# SC_ControlV2_0.net
KiCad netlist of a schematic drawn in Altium Designer
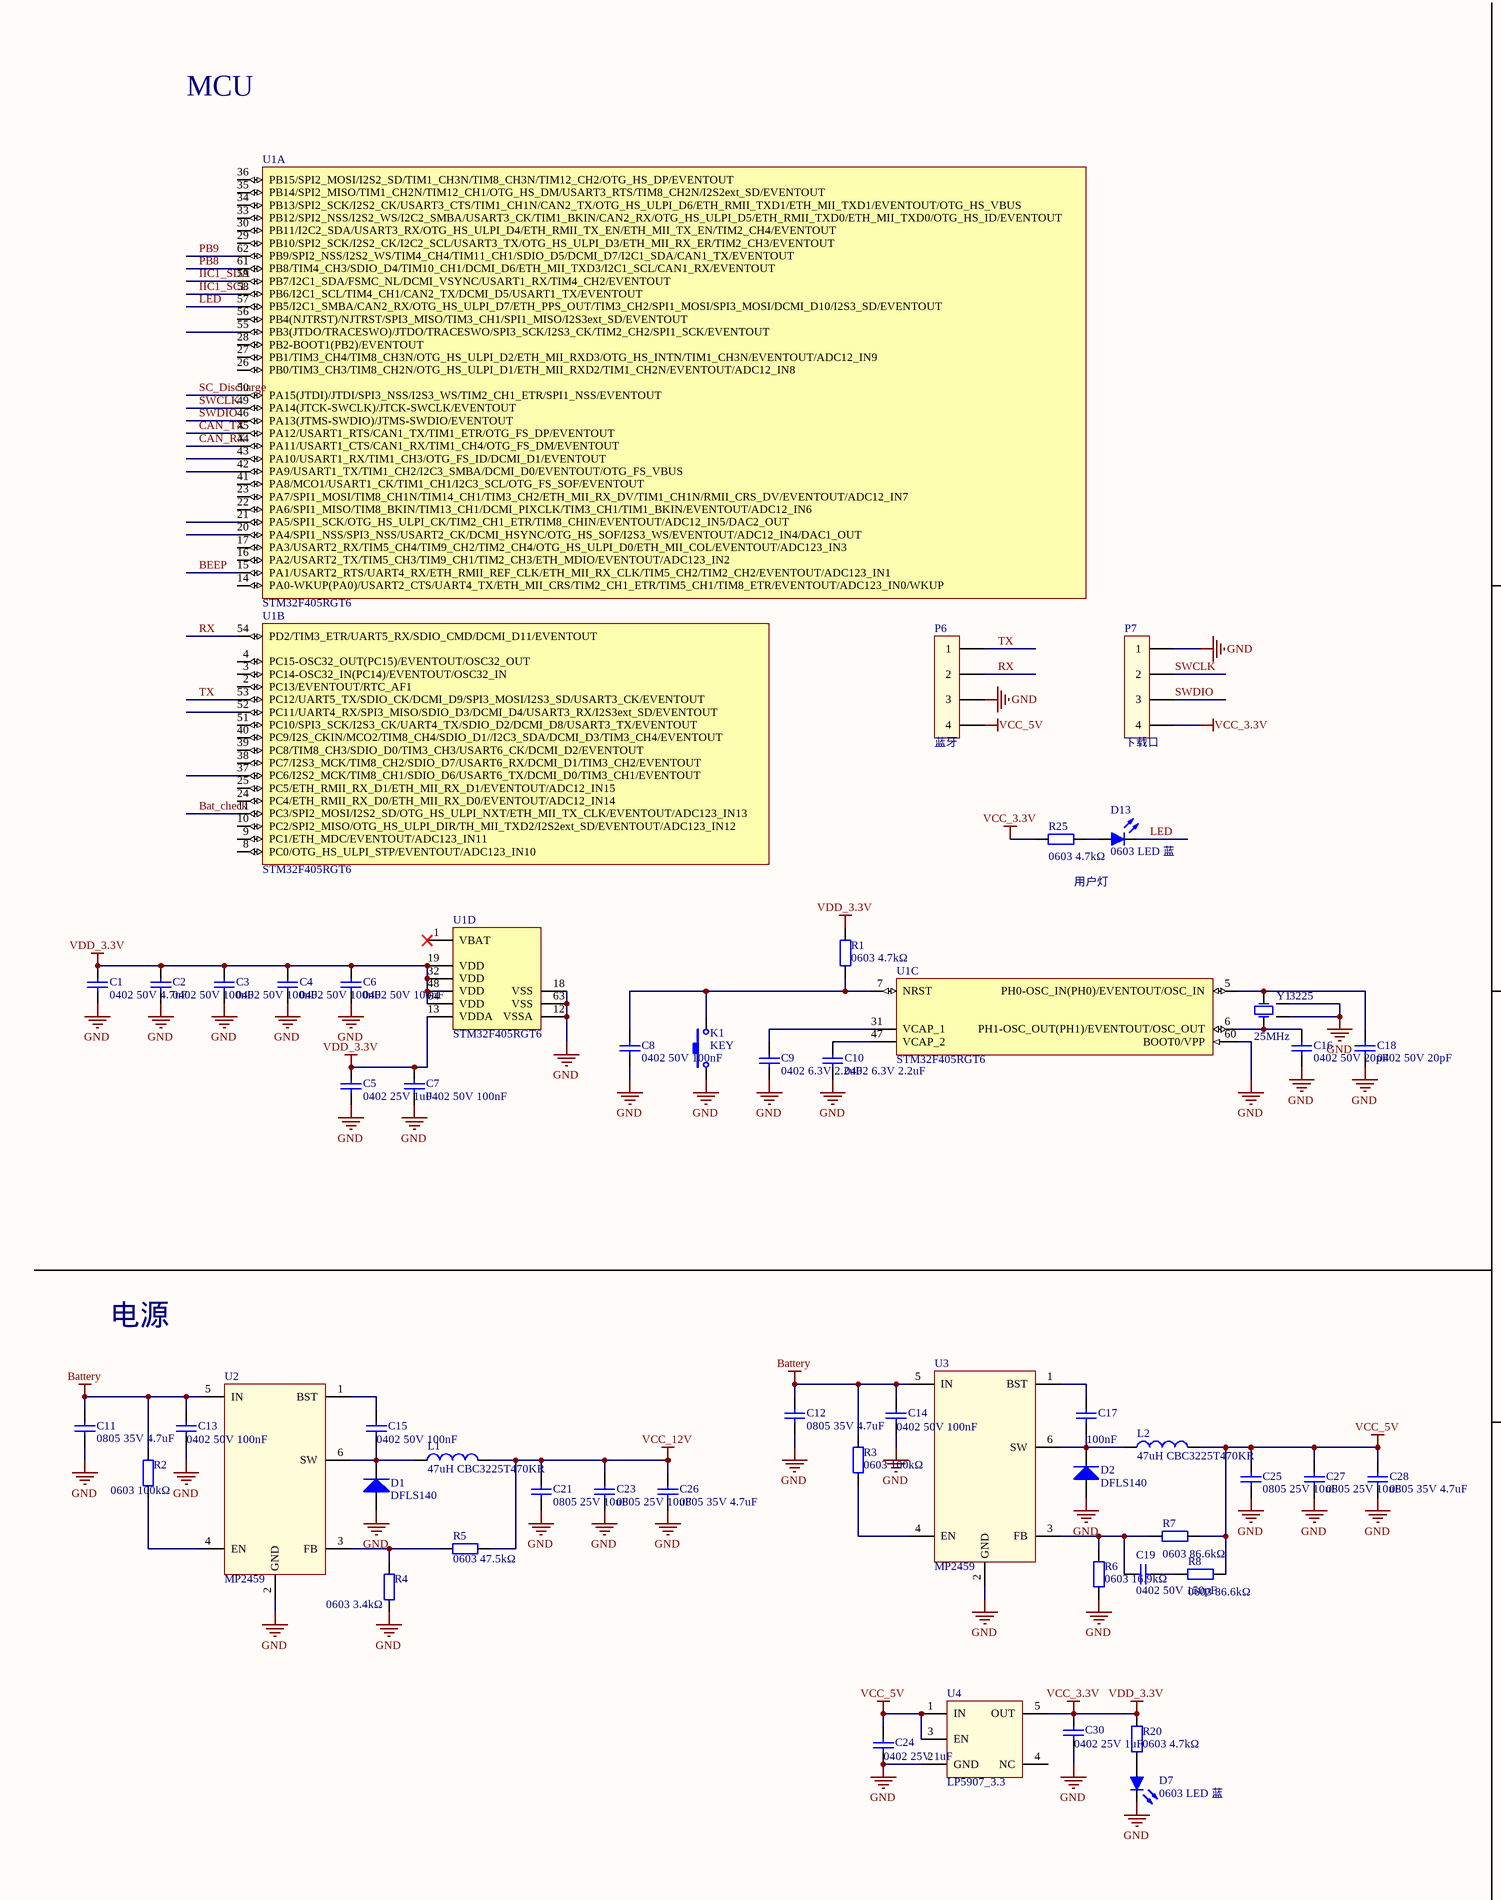
[diagram p0: SC_ControlV2.0.SchDoc, left]
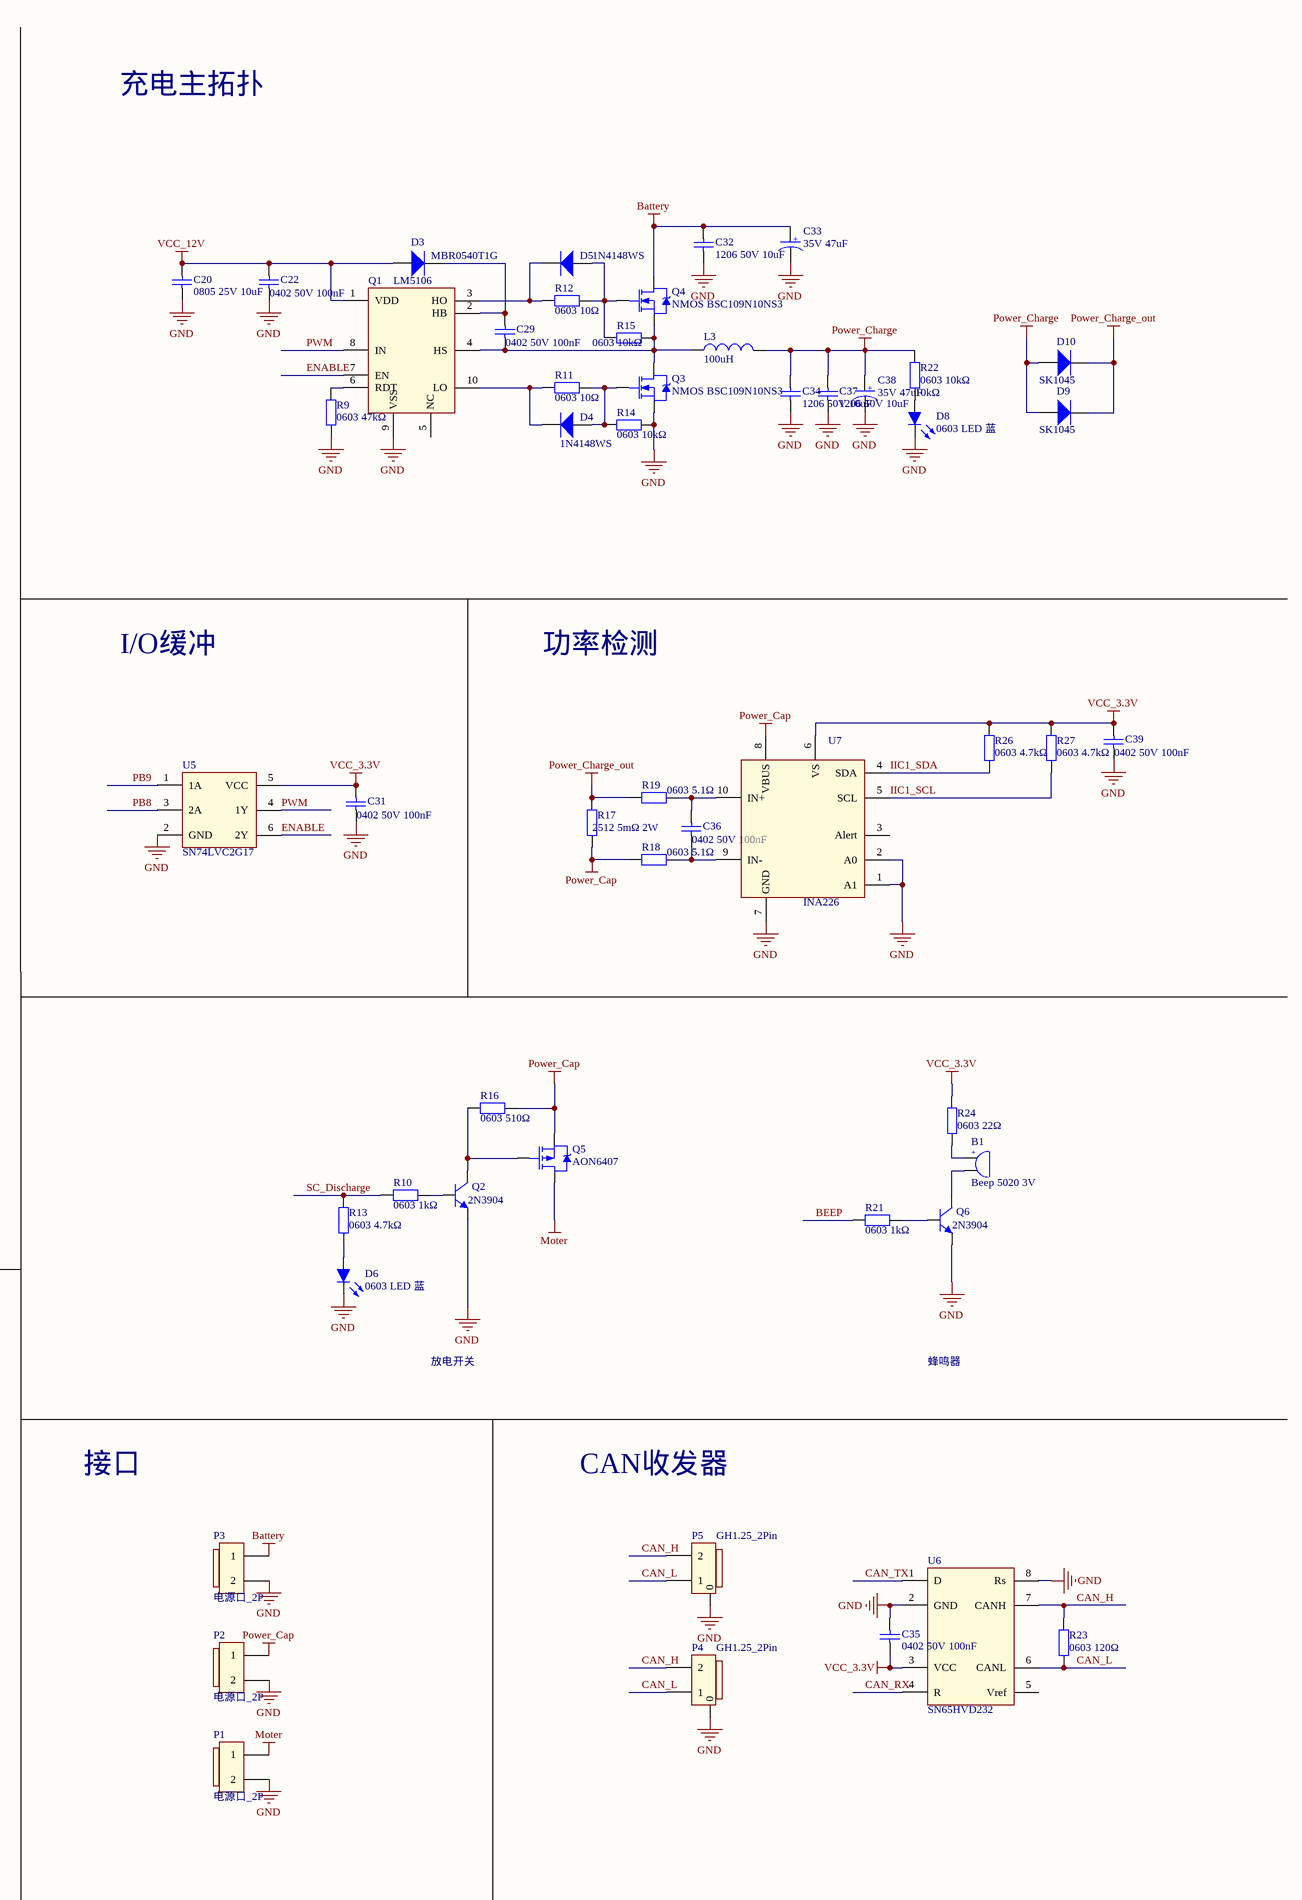
[diagram p1: SC_ControlV2.0.SchDoc, right]

(export (version "E")
  (design (tool "Eeschema 10.0.6"))
  (components
    (comp (ref "B1")
      (value "Beep 5020 3V")
      (footprint "Beep 5020")
      (libsource (lib "MyLib_zzy") (part "Beep"))
    )
    (comp (ref "C1") (value "0402 50V 4.7uF") (footprint "0402_C") (libsource (lib "MyLib_zzy") (part "Cap")))
    (comp (ref "C2") (value "0402 50V 100nF") (footprint "0402_C") (libsource (lib "MyLib_zzy") (part "Cap")))
    (comp (ref "C3") (value "0402 50V 100nF") (footprint "0402_C") (libsource (lib "MyLib_zzy") (part "Cap")))
    (comp (ref "C4") (value "0402 50V 100nF") (footprint "0402_C") (libsource (lib "MyLib_zzy") (part "Cap")))
    (comp (ref "C5") (value "0402 25V 1uF") (footprint "0402_C") (libsource (lib "MyLib_zzy") (part "Cap")))
    (comp (ref "C6") (value "0402 50V 100nF") (footprint "0402_C") (libsource (lib "MyLib_zzy") (part "Cap")))
    (comp (ref "C7") (value "0402 50V 100nF") (footprint "0402_C") (libsource (lib "MyLib_zzy") (part "Cap")))
    (comp (ref "C8") (value "0402 50V 100nF") (footprint "0402_C") (libsource (lib "MyLib_zzy") (part "Cap")))
    (comp (ref "C9")
      (value "0402 6.3V 2.2uF")
      (footprint "0402_C")
      (libsource (lib "MyLib_zzy") (part "Cap"))
    )
    (comp (ref "C10")
      (value "0402 6.3V 2.2uF")
      (footprint "0402_C")
      (libsource (lib "MyLib_zzy") (part "Cap"))
    )
    (comp (ref "C11")
      (value "0805 35V 4.7uF")
      (footprint "0805_C")
      (libsource (lib "MyLib_zzy") (part "Cap"))
    )
    (comp (ref "C12")
      (value "0805 35V 4.7uF")
      (footprint "0805_C")
      (libsource (lib "MyLib_zzy") (part "Cap"))
    )
    (comp (ref "C13")
      (value "0402 50V 100nF")
      (footprint "0402_C")
      (libsource (lib "MyLib_zzy") (part "Cap"))
    )
    (comp (ref "C14")
      (value "0402 50V 100nF")
      (footprint "0402_C")
      (libsource (lib "MyLib_zzy") (part "Cap"))
    )
    (comp (ref "C15")
      (value "0402 50V 100nF")
      (footprint "0402_C")
      (libsource (lib "MyLib_zzy") (part "Cap"))
    )
    (comp (ref "C16") (value "0402 50V 20pF") (footprint "0402_C") (libsource (lib "MyLib_zzy") (part "Cap")))
    (comp (ref "C17")
      (value "0402 50V 100nF")
      (footprint "0402_C")
      (fields (field (name "CAP") "100nF"))
      (libsource (lib "MyLib_zzy") (part "Cap"))
    )
    (comp (ref "C18") (value "0402 50V 20pF") (footprint "0402_C") (libsource (lib "MyLib_zzy") (part "Cap")))
    (comp (ref "C19")
      (value "0402 50V 150pF")
      (footprint "0603_C")
      (libsource (lib "MyLib_zzy") (part "Cap"))
    )
    (comp (ref "C20") (value "0805 25V 10uF") (footprint "0805_C") (libsource (lib "MyLib_zzy") (part "Cap")))
    (comp (ref "C21") (value "0805 25V 10uF") (footprint "0805_C") (libsource (lib "MyLib_zzy") (part "Cap")))
    (comp (ref "C22") (value "0402 50V 100nF") (footprint "0402_C") (libsource (lib "") (part "Cap_1")))
    (comp (ref "C23") (value "0805 25V 10uF") (footprint "0805_C") (libsource (lib "MyLib_zzy") (part "Cap")))
    (comp (ref "C24") (value "0402 25V 1uF") (footprint "0402_C") (libsource (lib "MyLib_zzy") (part "Cap")))
    (comp (ref "C25") (value "0805 25V 10uF") (footprint "0805_C") (libsource (lib "MyLib_zzy") (part "Cap")))
    (comp (ref "C26")
      (value "0805 35V 4.7uF")
      (footprint "0805_C")
      (libsource (lib "MyLib_zzy") (part "Cap"))
    )
    (comp (ref "C27") (value "0805 25V 10uF") (footprint "0805_C") (libsource (lib "MyLib_zzy") (part "Cap")))
    (comp (ref "C28")
      (value "0805 35V 4.7uF")
      (footprint "0805_C")
      (libsource (lib "MyLib_zzy") (part "Cap"))
    )
    (comp (ref "C29") (value "0402 50V 100nF") (footprint "0402_C") (libsource (lib "") (part "Cap_1")))
    (comp (ref "C30") (value "0402 25V 1uF") (footprint "0402_C") (libsource (lib "MyLib_zzy") (part "Cap")))
    (comp (ref "C31") (value "0402 50V 100nF") (footprint "0402_C") (libsource (lib "") (part "Cap_1")))
    (comp (ref "C32") (value "1206 50V 10uF") (footprint "1206_C") (libsource (lib "MyLib_zzy") (part "Cap")))
    (comp (ref "C33") (value "35V 47uF") (footprint "贴片铝电解_8") (libsource (lib "MyLib_zzy") (part "铝电解")))
    (comp (ref "C34") (value "1206 50V 10uF") (footprint "1206_C") (libsource (lib "MyLib_zzy") (part "Cap")))
    (comp (ref "C35")
      (value "0402 50V 100nF")
      (footprint "0402_C")
      (libsource (lib "MyLib_zzy") (part "Cap"))
    )
    (comp (ref "C36") (value "0402 50V 100nF") (footprint "0402_C") (libsource (lib "") (part "Cap_1")))
    (comp (ref "C37") (value "1206 50V 10uF") (footprint "1206_C") (libsource (lib "MyLib_zzy") (part "Cap")))
    (comp (ref "C38") (value "35V 47uF") (footprint "贴片铝电解_8") (libsource (lib "MyLib_zzy") (part "铝电解")))
    (comp (ref "C39") (value "0402 50V 100nF") (footprint "0402_C") (libsource (lib "") (part "Cap_1")))
    (comp (ref "D1")
      (value "DFLS140")
      (footprint "POWERDI_123")
      (libsource (lib "MyLib_zzy") (part "肖特基二极管"))
    )
    (comp (ref "D2")
      (value "DFLS140")
      (footprint "POWERDI_123")
      (libsource (lib "MyLib_zzy") (part "肖特基二极管"))
    )
    (comp (ref "D3")
      (value "MBR0540T1G")
      (footprint "SOD_123F")
      (libsource (lib "MyLib_zzy") (part "肖特基二极管"))
    )
    (comp (ref "D4") (value "1N4148WS") (footprint "SOD_323F") (libsource (lib "MyLib_zzy") (part "开关二极管")))
    (comp (ref "D5") (value "1N4148WS") (footprint "SOD_323F") (libsource (lib "MyLib_zzy") (part "开关二极管")))
    (comp (ref "D6") (value "0603 LED 蓝") (footprint "0603_LED") (libsource (lib "MyLib_zzy") (part "LED")))
    (comp (ref "D7") (value "0603 LED 蓝") (footprint "0603_LED") (libsource (lib "MyLib_zzy") (part "LED")))
    (comp (ref "D8") (value "0603 LED 蓝") (footprint "0603_LED") (libsource (lib "MyLib_zzy") (part "LED")))
    (comp (ref "D9")
      (value "SK1045")
      (footprint "MyLib_zzy:SMC")
      (libsource (lib "MyLib_zzy") (part "肖特基二极管"))
    )
    (comp (ref "D10")
      (value "SK1045")
      (footprint "MyLib_zzy:SMC")
      (libsource (lib "MyLib_zzy") (part "肖特基二极管"))
    )
    (comp (ref "D13") (value "0603 LED 蓝") (footprint "0603_LED") (libsource (lib "MyLib_zzy") (part "LED")))
    (comp (ref "K1") (value "KEY") (footprint "按键_3*4") (libsource (lib "MyLib_zzy") (part "按键_小")))
    (comp (ref "L1")
      (value "47uH CBC3225T470KR")
      (footprint "1210_L")
      (libsource (lib "MyLib_zzy") (part "电感"))
    )
    (comp (ref "L2")
      (value "47uH CBC3225T470KR")
      (footprint "1210_L")
      (libsource (lib "MyLib_zzy") (part "电感"))
    )
    (comp (ref "L3") (value "100uH") (footprint "绕线电感_14mm") (libsource (lib "MyLib_zzy") (part "电感")))
    (comp (ref "P1") (value "电源口_2P") (footprint "电源口_2P") (libsource (lib "MyLib_zzy") (part "电源口_2P")))
    (comp (ref "P2") (value "电源口_2P") (footprint "电源口_2P") (libsource (lib "MyLib_zzy") (part "电源口_2P")))
    (comp (ref "P3") (value "电源口_2P") (footprint "电源口_2P") (libsource (lib "MyLib_zzy") (part "电源口_2P")))
    (comp (ref "P4")
      (value "GH1.25_2Pin")
      (footprint "GH1.25_2Pin")
      (libsource (lib "MyLib_zzy") (part "GH1.25_2Pin"))
    )
    (comp (ref "P5")
      (value "GH1.25_2Pin")
      (footprint "GH1.25_2Pin")
      (libsource (lib "MyLib_zzy") (part "GH1.25_2Pin"))
    )
    (comp (ref "P6") (value "蓝牙") (footprint "HDR_4Pin") (libsource (lib "MyLib_zzy") (part "HDR_4Pin")))
    (comp (ref "P7") (value "下载口") (footprint "HDR_4Pin") (libsource (lib "MyLib_zzy") (part "HDR_4Pin")))
    (comp (ref "Q1") (value "LM5106") (footprint "VSSOP10") (libsource (lib "MyLib_zzy") (part "LM5106")))
    (comp (ref "Q2") (value "2N3904") (footprint "SOT23_3") (libsource (lib "MyLib_zzy") (part "NPN")))
    (comp (ref "Q3")
      (value "NMOS BSC109N10NS3")
      (footprint "PG_TDSON_8")
      (libsource (lib "MyLib_zzy") (part "NMOS"))
    )
    (comp (ref "Q4")
      (value "NMOS BSC109N10NS3")
      (footprint "PG_TDSON_8")
      (libsource (lib "MyLib_zzy") (part "NMOS"))
    )
    (comp (ref "Q5") (value "AON6407") (footprint "DFN_5x6") (libsource (lib "MyLib_zzy") (part "PMOS")))
    (comp (ref "Q6") (value "2N3904") (footprint "SOT23_3") (libsource (lib "MyLib_zzy") (part "NPN")))
    (comp (ref "R1") (value "0603 4.7kΩ") (footprint "0603 _R") (libsource (lib "") (part "Res_1")))
    (comp (ref "R2") (value "0603 100kΩ") (footprint "0603 _R") (libsource (lib "") (part "Res_1")))
    (comp (ref "R3") (value "0603 100kΩ") (footprint "0603 _R") (libsource (lib "") (part "Res_2")))
    (comp (ref "R4") (value "0603 3.4kΩ") (footprint "0603 _R") (libsource (lib "") (part "Res_1")))
    (comp (ref "R5") (value "0603 47.5kΩ") (footprint "0603 _R") (libsource (lib "MyLib_zzy") (part "Res")))
    (comp (ref "R6") (value "0603 16.9kΩ") (footprint "0603 _R") (libsource (lib "") (part "Res_2")))
    (comp (ref "R7") (value "0603 86.6kΩ") (footprint "0603 _R") (libsource (lib "MyLib_zzy") (part "Res")))
    (comp (ref "R8") (value "0603 86.6kΩ") (footprint "0603 _R") (libsource (lib "MyLib_zzy") (part "Res")))
    (comp (ref "R9") (value "0603 47kΩ") (footprint "0603 _R") (libsource (lib "") (part "Res_2")))
    (comp (ref "R10") (value "0603 1kΩ") (footprint "0603 _R") (libsource (lib "MyLib_zzy") (part "Res")))
    (comp (ref "R11") (value "0603 10Ω") (footprint "0603 _R") (libsource (lib "MyLib_zzy") (part "Res")))
    (comp (ref "R12") (value "0603 10Ω") (footprint "0603 _R") (libsource (lib "MyLib_zzy") (part "Res")))
    (comp (ref "R13") (value "0603 4.7kΩ") (footprint "0603 _R") (libsource (lib "") (part "Res_1")))
    (comp (ref "R14") (value "0603 10kΩ") (footprint "0603 _R") (libsource (lib "MyLib_zzy") (part "Res")))
    (comp (ref "R15") (value "0603 10kΩ") (footprint "0603 _R") (libsource (lib "MyLib_zzy") (part "Res")))
    (comp (ref "R16") (value "0603 510Ω") (footprint "0603 _R") (libsource (lib "MyLib_zzy") (part "Res")))
    (comp (ref "R17") (value "2512 5mΩ 2W") (footprint "2512_R") (libsource (lib "") (part "Res_1")))
    (comp (ref "R18") (value "0603 5.1Ω") (footprint "0603 _R") (libsource (lib "MyLib_zzy") (part "Res")))
    (comp (ref "R19") (value "0603 5.1Ω") (footprint "0603 _R") (libsource (lib "MyLib_zzy") (part "Res")))
    (comp (ref "R20") (value "0603 4.7kΩ") (footprint "0603 _R") (libsource (lib "") (part "Res_1")))
    (comp (ref "R21") (value "0603 1kΩ") (footprint "0603 _R") (libsource (lib "") (part "Res_3")))
    (comp (ref "R22")
      (value "0603 10kΩ")
      (footprint "0603 _R")
      (fields (field (name "RES") "10kΩ"))
      (libsource (lib "") (part "Res_1"))
    )
    (comp (ref "R23") (value "0603 120Ω") (footprint "0603 _R") (libsource (lib "") (part "Res_2")))
    (comp (ref "R24") (value "0603 22Ω") (footprint "0603 _R") (libsource (lib "") (part "Res_2")))
    (comp (ref "R25") (value "0603 4.7kΩ") (footprint "0603 _R") (libsource (lib "MyLib_zzy") (part "Res")))
    (comp (ref "R26") (value "0603 4.7kΩ") (footprint "0603 _R") (libsource (lib "") (part "Res_2")))
    (comp (ref "R27") (value "0603 4.7kΩ") (footprint "0603 _R") (libsource (lib "") (part "Res_2")))
    (comp (ref "U1")
      (value "STM32F405RGT6")
      (footprint "LQFP64")
      (libsource (lib "MyLib_zzy") (part "STM32F405RGT6"))
    )
    (comp (ref "U2") (value "MP2459") (footprint "SOT23_6") (libsource (lib "MyLib_zzy") (part "MP2459")))
    (comp (ref "U3") (value "MP2459") (footprint "SOT23_6") (libsource (lib "MyLib_zzy") (part "MP2459")))
    (comp (ref "U4") (value "LP5907_3.3") (footprint "SOT23_5") (libsource (lib "MyLib_zzy") (part "LP5907")))
    (comp (ref "U5")
      (value "SN74LVC2G17")
      (footprint "SOT23_6")
      (libsource (lib "MyLib_zzy") (part "SN74LVC2G17"))
    )
    (comp (ref "U6")
      (value "SN65HVD232")
      (footprint "MyLib_zzy:SOP8")
      (libsource (lib "MyLib_zzy") (part "SN65HVD232"))
    )
    (comp (ref "U7") (value "INA226") (footprint "VSSOP10") (libsource (lib "MyLib_zzy") (part "INA226")))
    (comp (ref "Y1")
      (value "3225")
      (footprint "SMD-3225-4P")
      (fields (field (name "无源晶振") "25MHz"))
      (libsource (lib "MyLib_zzy") (part "无源晶振_4Pin"))
    )
  )
  (nets
    (net (code "1") (name "/BEEP") (class "Default")
      (node (ref "R21") (pin "1") (pinfunction "1_1") (pintype "passive"))
      (node (ref "U1") (pin "15") (pinfunction "PA1/USART2_RTS/UART4_RX/ETH_RMII_REF_CLK/ETH_MII_RX_CLK/TIM5_CH2/TIM2_CH2/EVENTOUT/ADC123_IN1_15") (pintype "bidirectional"))
    )
    (net (code "2") (name "/Bat_check") (class "Default")
      (node (ref "U1") (pin "11") (pinfunction "PC3/SPI2_MOSI/I2S2_SD/OTG_HS_ULPI_NXT/ETH_MII_TX_CLK/EVENTOUT/ADC123_IN13_11") (pintype "bidirectional"))
    )
    (net (code "3") (name "/CAN_H") (class "Default")
      (node (ref "P4") (pin "2") (pinfunction "2_2") (pintype "passive"))
      (node (ref "P5") (pin "2") (pinfunction "2_2") (pintype "passive"))
      (node (ref "R23") (pin "1") (pinfunction "1_1") (pintype "passive"))
      (node (ref "U6") (pin "7") (pinfunction "CANH_7") (pintype "passive"))
    )
    (net (code "4") (name "/CAN_L") (class "Default")
      (node (ref "P4") (pin "1") (pinfunction "1_1") (pintype "passive"))
      (node (ref "P5") (pin "1") (pinfunction "1_1") (pintype "passive"))
      (node (ref "R23") (pin "2") (pinfunction "2_2") (pintype "passive"))
      (node (ref "U6") (pin "6") (pinfunction "CANL_6") (pintype "passive"))
    )
    (net (code "5") (name "/CAN_RX") (class "Default")
      (node (ref "U1") (pin "44") (pinfunction "PA11/USART1_CTS/CAN1_RX/TIM1_CH4/OTG_FS_DM/EVENTOUT_44") (pintype "bidirectional"))
      (node (ref "U6") (pin "4") (pinfunction "R_4") (pintype "passive"))
    )
    (net (code "6") (name "/CAN_TX") (class "Default")
      (node (ref "U1") (pin "45") (pinfunction "PA12/USART1_RTS/CAN1_TX/TIM1_ETR/OTG_FS_DP/EVENTOUT_45") (pintype "bidirectional"))
      (node (ref "U6") (pin "1") (pinfunction "D_1") (pintype "passive"))
    )
    (net (code "7") (name "/ENABLE") (class "Default")
      (node (ref "Q1") (pin "7") (pinfunction "EN_7") (pintype "passive"))
      (node (ref "U5") (pin "6") (pinfunction "2Y_6") (pintype "passive"))
    )
    (net (code "8") (name "/IIC1_SCL") (class "Default")
      (node (ref "R27") (pin "2") (pinfunction "2_2") (pintype "passive"))
      (node (ref "U1") (pin "58") (pinfunction "PB6/I2C1_SCL/TIM4_CH1/CAN2_TX/DCMI_D5/USART1_TX/EVENTOUT_58") (pintype "bidirectional"))
      (node (ref "U7") (pin "5") (pinfunction "SCL_5") (pintype "passive"))
    )
    (net (code "9") (name "/IIC1_SDA") (class "Default")
      (node (ref "R26") (pin "2") (pinfunction "2_2") (pintype "passive"))
      (node (ref "U1") (pin "59") (pinfunction "PB7/I2C1_SDA/FSMC_NL/DCMI_VSYNC/USART1_RX/TIM4_CH2/EVENTOUT_59") (pintype "bidirectional"))
      (node (ref "U7") (pin "4") (pinfunction "SDA_4") (pintype "passive"))
    )
    (net (code "10") (name "/LED") (class "Default")
      (node (ref "D13") (pin "K") (pinfunction "K_K") (pintype "passive"))
      (node (ref "U1") (pin "57") (pinfunction "PB5/I2C1_SMBA/CAN2_RX/OTG_HS_ULPI_D7/ETH_PPS_OUT/TIM3_CH2/SPI1_MOSI/SPI3_MOSI/DCMI_D10/I2S3_SD/EVENTOUT_57") (pintype "bidirectional"))
    )
    (net (code "11") (name "/PB8") (class "Default")
      (node (ref "U1") (pin "61") (pinfunction "PB8/TIM4_CH3/SDIO_D4/TIM10_CH1/DCMI_D6/ETH_MII_TXD3/I2C1_SCL/CAN1_RX/EVENTOUT_61") (pintype "bidirectional"))
      (node (ref "U5") (pin "3") (pinfunction "2A_3") (pintype "passive"))
    )
    (net (code "12") (name "/PB9") (class "Default")
      (node (ref "U1") (pin "62") (pinfunction "PB9/SPI2_NSS/I2S2_WS/TIM4_CH4/TIM11_CH1/SDIO_D5/DCMI_D7/I2C1_SDA/CAN1_TX/EVENTOUT_62") (pintype "bidirectional"))
      (node (ref "U5") (pin "1") (pinfunction "1A_1") (pintype "passive"))
    )
    (net (code "13") (name "/PWM") (class "Default")
      (node (ref "Q1") (pin "8") (pinfunction "IN_8") (pintype "passive"))
      (node (ref "U5") (pin "4") (pinfunction "1Y_4") (pintype "passive"))
    )
    (net (code "14") (name "/RX") (class "Default")
      (node (ref "P6") (pin "2") (pinfunction "2_2") (pintype "passive"))
      (node (ref "U1") (pin "54") (pinfunction "PD2/TIM3_ETR/UART5_RX/SDIO_CMD/DCMI_D11/EVENTOUT_54") (pintype "bidirectional"))
    )
    (net (code "15") (name "/SC_Discharge") (class "Default")
      (node (ref "R10") (pin "2") (pinfunction "2_2") (pintype "passive"))
      (node (ref "R13") (pin "2") (pinfunction "2_2") (pintype "passive"))
      (node (ref "U1") (pin "50") (pinfunction "PA15(JTDI)/JTDI/SPI3_NSS/I2S3_WS/TIM2_CH1_ETR/SPI1_NSS/EVENTOUT_50") (pintype "bidirectional"))
    )
    (net (code "16") (name "/SWCLK") (class "Default")
      (node (ref "P7") (pin "2") (pinfunction "2_2") (pintype "passive"))
      (node (ref "U1") (pin "49") (pinfunction "PA14(JTCK-SWCLK)/JTCK-SWCLK/EVENTOUT_49") (pintype "bidirectional"))
    )
    (net (code "17") (name "/SWDIO") (class "Default")
      (node (ref "P7") (pin "3") (pinfunction "3_3") (pintype "passive"))
      (node (ref "U1") (pin "46") (pinfunction "PA13(JTMS-SWDIO)/JTMS-SWDIO/EVENTOUT_46") (pintype "bidirectional"))
    )
    (net (code "18") (name "/TX") (class "Default")
      (node (ref "P6") (pin "1") (pinfunction "1_1") (pintype "passive"))
      (node (ref "U1") (pin "53") (pinfunction "PC12/UART5_TX/SDIO_CK/DCMI_D9/SPI3_MOSI/I2S3_SD/USART3_CK/EVENTOUT_53") (pintype "bidirectional"))
    )
    (net (code "19") (name "Battery") (class "Default")
      (node (ref "C11") (pin "1") (pinfunction "1_1") (pintype "passive"))
      (node (ref "C12") (pin "1") (pinfunction "1_1") (pintype "passive"))
      (node (ref "C13") (pin "1") (pinfunction "1_1") (pintype "passive"))
      (node (ref "C14") (pin "1") (pinfunction "1_1") (pintype "passive"))
      (node (ref "C32") (pin "1") (pinfunction "1_1") (pintype "passive"))
      (node (ref "C33") (pin "1") (pinfunction "A_1") (pintype "passive"))
      (node (ref "P3") (pin "1") (pinfunction "1_1") (pintype "passive"))
      (node (ref "Q4") (pin "2") (pinfunction "D_2") (pintype "passive"))
      (node (ref "R2") (pin "2") (pinfunction "2_2") (pintype "passive"))
      (node (ref "R3") (pin "1") (pinfunction "1_1") (pintype "passive"))
      (node (ref "U2") (pin "5") (pinfunction "IN_5") (pintype "passive"))
      (node (ref "U3") (pin "5") (pinfunction "IN_5") (pintype "passive"))
    )
    (net (code "20") (name "GND") (class "Default")
      (node (ref "C1") (pin "2") (pinfunction "2_2") (pintype "passive"))
      (node (ref "C10") (pin "2") (pinfunction "2_2") (pintype "passive"))
      (node (ref "C11") (pin "2") (pinfunction "2_2") (pintype "passive"))
      (node (ref "C12") (pin "2") (pinfunction "2_2") (pintype "passive"))
      (node (ref "C13") (pin "2") (pinfunction "2_2") (pintype "passive"))
      (node (ref "C14") (pin "2") (pinfunction "2_2") (pintype "passive"))
      (node (ref "C16") (pin "1") (pinfunction "1_1") (pintype "passive"))
      (node (ref "C18") (pin "1") (pinfunction "1_1") (pintype "passive"))
      (node (ref "C2") (pin "2") (pinfunction "2_2") (pintype "passive"))
      (node (ref "C20") (pin "2") (pinfunction "2_2") (pintype "passive"))
      (node (ref "C21") (pin "2") (pinfunction "2_2") (pintype "passive"))
      (node (ref "C22") (pin "2") (pinfunction "2_2") (pintype "passive"))
      (node (ref "C23") (pin "2") (pinfunction "2_2") (pintype "passive"))
      (node (ref "C24") (pin "2") (pinfunction "2_2") (pintype "passive"))
      (node (ref "C25") (pin "2") (pinfunction "2_2") (pintype "passive"))
      (node (ref "C26") (pin "2") (pinfunction "2_2") (pintype "passive"))
      (node (ref "C27") (pin "2") (pinfunction "2_2") (pintype "passive"))
      (node (ref "C28") (pin "2") (pinfunction "2_2") (pintype "passive"))
      (node (ref "C3") (pin "2") (pinfunction "2_2") (pintype "passive"))
      (node (ref "C30") (pin "2") (pinfunction "2_2") (pintype "passive"))
      (node (ref "C31") (pin "2") (pinfunction "2_2") (pintype "passive"))
      (node (ref "C32") (pin "2") (pinfunction "2_2") (pintype "passive"))
      (node (ref "C33") (pin "2") (pinfunction "15_2") (pintype "passive"))
      (node (ref "C34") (pin "2") (pinfunction "2_2") (pintype "passive"))
      (node (ref "C35") (pin "2") (pinfunction "2_2") (pintype "passive"))
      (node (ref "C37") (pin "2") (pinfunction "2_2") (pintype "passive"))
      (node (ref "C38") (pin "2") (pinfunction "15_2") (pintype "passive"))
      (node (ref "C39") (pin "2") (pinfunction "2_2") (pintype "passive"))
      (node (ref "C4") (pin "2") (pinfunction "2_2") (pintype "passive"))
      (node (ref "C5") (pin "2") (pinfunction "2_2") (pintype "passive"))
      (node (ref "C6") (pin "2") (pinfunction "2_2") (pintype "passive"))
      (node (ref "C7") (pin "2") (pinfunction "2_2") (pintype "passive"))
      (node (ref "C8") (pin "1") (pinfunction "1_1") (pintype "passive"))
      (node (ref "C9") (pin "2") (pinfunction "2_2") (pintype "passive"))
      (node (ref "D1") (pin "1") (pinfunction "A_1") (pintype "passive"))
      (node (ref "D2") (pin "1") (pinfunction "A_1") (pintype "passive"))
      (node (ref "D6") (pin "K") (pinfunction "K_K") (pintype "passive"))
      (node (ref "D7") (pin "K") (pinfunction "K_K") (pintype "passive"))
      (node (ref "D8") (pin "K") (pinfunction "K_K") (pintype "passive"))
      (node (ref "K1") (pin "1") (pinfunction "1_1") (pintype "passive"))
      (node (ref "P1") (pin "2") (pinfunction "2_2") (pintype "passive"))
      (node (ref "P2") (pin "2") (pinfunction "2_2") (pintype "passive"))
      (node (ref "P3") (pin "2") (pinfunction "2_2") (pintype "passive"))
      (node (ref "P4") (pin "0") (pinfunction "0_0") (pintype "passive"))
      (node (ref "P5") (pin "0") (pinfunction "0_0") (pintype "passive"))
      (node (ref "P6") (pin "3") (pinfunction "3_3") (pintype "passive"))
      (node (ref "P7") (pin "1") (pinfunction "1_1") (pintype "passive"))
      (node (ref "Q1") (pin "9") (pinfunction "VSS_9") (pintype "passive"))
      (node (ref "Q2") (pin "2") (pinfunction "E_2") (pintype "passive"))
      (node (ref "Q3") (pin "3") (pinfunction "S_3") (pintype "passive"))
      (node (ref "Q6") (pin "2") (pinfunction "E_2") (pintype "passive"))
      (node (ref "R14") (pin "1") (pinfunction "1_1") (pintype "passive"))
      (node (ref "R4") (pin "1") (pinfunction "1_1") (pintype "passive"))
      (node (ref "R6") (pin "2") (pinfunction "2_2") (pintype "passive"))
      (node (ref "R9") (pin "2") (pinfunction "2_2") (pintype "passive"))
      (node (ref "U1") (pin "12") (pinfunction "VSSA_12") (pintype "power_in"))
      (node (ref "U1") (pin "18") (pinfunction "VSS_18") (pintype "power_in"))
      (node (ref "U1") (pin "60") (pinfunction "BOOT0/VPP_60") (pintype "input"))
      (node (ref "U1") (pin "63") (pinfunction "VSS_63") (pintype "power_in"))
      (node (ref "U2") (pin "2") (pinfunction "GND_2") (pintype "passive"))
      (node (ref "U3") (pin "2") (pinfunction "GND_2") (pintype "passive"))
      (node (ref "U4") (pin "2") (pinfunction "GND_2") (pintype "passive"))
      (node (ref "U5") (pin "2") (pinfunction "GND_2") (pintype "passive"))
      (node (ref "U6") (pin "2") (pinfunction "GND_2") (pintype "passive"))
      (node (ref "U6") (pin "8") (pinfunction "Rs_8") (pintype "passive"))
      (node (ref "U7") (pin "1") (pinfunction "A1_1") (pintype "passive"))
      (node (ref "U7") (pin "2") (pinfunction "A0_2") (pintype "passive"))
      (node (ref "U7") (pin "7") (pinfunction "GND_7") (pintype "passive"))
      (node (ref "Y1") (pin "2") (pinfunction "GND_2") (pintype "passive"))
      (node (ref "Y1") (pin "4") (pinfunction "GND_4") (pintype "passive"))
    )
    (net (code "21") (name "Moter") (class "Default")
      (node (ref "P1") (pin "1") (pinfunction "1_1") (pintype "passive"))
      (node (ref "Q5") (pin "2") (pinfunction "D_2") (pintype "passive"))
    )
    (net (code "22") (name "Net-(B1-Pad1)") (class "Default")
      (node (ref "B1") (pin "1") (pinfunction "1_1") (pintype "passive"))
      (node (ref "R24") (pin "2") (pinfunction "2_2") (pintype "passive"))
    )
    (net (code "23") (name "Net-(C19-Pad2)") (class "Default")
      (node (ref "C19") (pin "2") (pinfunction "2_2") (pintype "passive"))
      (node (ref "R8") (pin "2") (pinfunction "2_2") (pintype "passive"))
    )
    (net (code "24") (name "Net-(D1-K)") (class "Default")
      (node (ref "C15") (pin "2") (pinfunction "2_2") (pintype "passive"))
      (node (ref "D1") (pin "2") (pinfunction "K_2") (pintype "passive"))
      (node (ref "L1") (pin "1") (pinfunction "1_1") (pintype "passive"))
      (node (ref "U2") (pin "6") (pinfunction "SW_6") (pintype "passive"))
    )
    (net (code "25") (name "Net-(D2-K)") (class "Default")
      (node (ref "C17") (pin "2") (pinfunction "2_2") (pintype "passive"))
      (node (ref "D2") (pin "2") (pinfunction "K_2") (pintype "passive"))
      (node (ref "L2") (pin "1") (pinfunction "1_1") (pintype "passive"))
      (node (ref "U3") (pin "6") (pinfunction "SW_6") (pintype "passive"))
    )
    (net (code "26") (name "Net-(D3-K)") (class "Default")
      (node (ref "C29") (pin "1") (pinfunction "1_1") (pintype "passive"))
      (node (ref "D3") (pin "2") (pinfunction "K_2") (pintype "passive"))
      (node (ref "Q1") (pin "2") (pinfunction "HB_2") (pintype "passive"))
    )
    (net (code "27") (name "Net-(D4-A)") (class "Default")
      (node (ref "D4") (pin "1") (pinfunction "A_1") (pintype "passive"))
      (node (ref "Q3") (pin "1") (pinfunction "G_1") (pintype "passive"))
      (node (ref "R11") (pin "1") (pinfunction "1_1") (pintype "passive"))
      (node (ref "R14") (pin "2") (pinfunction "2_2") (pintype "passive"))
    )
    (net (code "28") (name "Net-(D4-K)") (class "Default")
      (node (ref "D4") (pin "2") (pinfunction "K_2") (pintype "passive"))
      (node (ref "Q1") (pin "10") (pinfunction "LO_10") (pintype "passive"))
      (node (ref "R11") (pin "2") (pinfunction "2_2") (pintype "passive"))
    )
    (net (code "29") (name "Net-(D5-A)") (class "Default")
      (node (ref "D5") (pin "1") (pinfunction "A_1") (pintype "passive"))
      (node (ref "Q4") (pin "1") (pinfunction "G_1") (pintype "passive"))
      (node (ref "R12") (pin "1") (pinfunction "1_1") (pintype "passive"))
      (node (ref "R15") (pin "2") (pinfunction "2_2") (pintype "passive"))
    )
    (net (code "30") (name "Net-(D5-K)") (class "Default")
      (node (ref "D5") (pin "2") (pinfunction "K_2") (pintype "passive"))
      (node (ref "Q1") (pin "3") (pinfunction "HO_3") (pintype "passive"))
      (node (ref "R12") (pin "2") (pinfunction "2_2") (pintype "passive"))
    )
    (net (code "31") (name "Net-(D6-PadA)") (class "Default")
      (node (ref "D6") (pin "A") (pinfunction "A_A") (pintype "passive"))
      (node (ref "R13") (pin "1") (pinfunction "1_1") (pintype "passive"))
    )
    (net (code "32") (name "Net-(D7-PadA)") (class "Default")
      (node (ref "D7") (pin "A") (pinfunction "A_A") (pintype "passive"))
      (node (ref "R20") (pin "1") (pinfunction "1_1") (pintype "passive"))
    )
    (net (code "33") (name "Net-(D8-PadA)") (class "Default")
      (node (ref "D8") (pin "A") (pinfunction "A_A") (pintype "passive"))
      (node (ref "R22") (pin "1") (pinfunction "1_1") (pintype "passive"))
    )
    (net (code "34") (name "Net-(D13-PadA)") (class "Default")
      (node (ref "D13") (pin "A") (pinfunction "A_A") (pintype "passive"))
      (node (ref "R25") (pin "1") (pinfunction "1_1") (pintype "passive"))
    )
    (net (code "35") (name "Net-(Q1-HS)") (class "Default")
      (node (ref "C29") (pin "2") (pinfunction "2_2") (pintype "passive"))
      (node (ref "L3") (pin "1") (pinfunction "1_1") (pintype "passive"))
      (node (ref "Q1") (pin "4") (pinfunction "HS_4") (pintype "passive"))
      (node (ref "Q3") (pin "2") (pinfunction "D_2") (pintype "passive"))
      (node (ref "Q4") (pin "3") (pinfunction "S_3") (pintype "passive"))
      (node (ref "R15") (pin "1") (pinfunction "1_1") (pintype "passive"))
    )
    (net (code "36") (name "Net-(Q1-RDT)") (class "Default")
      (node (ref "Q1") (pin "6") (pinfunction "RDT_6") (pintype "passive"))
      (node (ref "R9") (pin "1") (pinfunction "1_1") (pintype "passive"))
    )
    (net (code "37") (name "Net-(Q2-B)") (class "Default")
      (node (ref "Q2") (pin "1") (pinfunction "B_1") (pintype "passive"))
      (node (ref "R10") (pin "1") (pinfunction "1_1") (pintype "passive"))
    )
    (net (code "38") (name "Net-(Q2-C)") (class "Default")
      (node (ref "Q2") (pin "3") (pinfunction "C_3") (pintype "passive"))
      (node (ref "Q5") (pin "1") (pinfunction "G_1") (pintype "passive"))
      (node (ref "R16") (pin "2") (pinfunction "2_2") (pintype "passive"))
    )
    (net (code "39") (name "Net-(Q6-B)") (class "Default")
      (node (ref "Q6") (pin "1") (pinfunction "B_1") (pintype "passive"))
      (node (ref "R21") (pin "2") (pinfunction "2_2") (pintype "passive"))
    )
    (net (code "40") (name "Net-(Q6-C)") (class "Default")
      (node (ref "B1") (pin "2") (pinfunction "2_2") (pintype "passive"))
      (node (ref "Q6") (pin "3") (pinfunction "C_3") (pintype "passive"))
    )
    (net (code "41") (name "Net-(U1C-NRST)") (class "Default")
      (node (ref "C8") (pin "2") (pinfunction "2_2") (pintype "passive"))
      (node (ref "K1") (pin "2") (pinfunction "2_2") (pintype "passive"))
      (node (ref "R1") (pin "1") (pinfunction "1_1") (pintype "passive"))
      (node (ref "U1") (pin "7") (pinfunction "NRST_7") (pintype "bidirectional"))
    )
    (net (code "42") (name "Net-(U1C-PH0-OSC_IN(PH0){slash}EVENTOUT{slash}OSC_IN)") (class "Default")
      (node (ref "C18") (pin "2") (pinfunction "2_2") (pintype "passive"))
      (node (ref "U1") (pin "5") (pinfunction "PH0-OSC_IN(PH0)/EVENTOUT/OSC_IN_5") (pintype "bidirectional"))
      (node (ref "Y1") (pin "3") (pinfunction "OSC1_3") (pintype "passive"))
    )
    (net (code "43") (name "Net-(U1C-PH1-OSC_OUT(PH1){slash}EVENTOUT{slash}OSC_OUT)") (class "Default")
      (node (ref "C16") (pin "2") (pinfunction "2_2") (pintype "passive"))
      (node (ref "U1") (pin "6") (pinfunction "PH1-OSC_OUT(PH1)/EVENTOUT/OSC_OUT_6") (pintype "bidirectional"))
      (node (ref "Y1") (pin "1") (pinfunction "OSC2_1") (pintype "passive"))
    )
    (net (code "44") (name "Net-(U1C-VCAP_1)") (class "Default")
      (node (ref "C9") (pin "1") (pinfunction "1_1") (pintype "passive"))
      (node (ref "U1") (pin "31") (pinfunction "VCAP_1_31") (pintype "power_in"))
    )
    (net (code "45") (name "Net-(U1C-VCAP_2)") (class "Default")
      (node (ref "C10") (pin "1") (pinfunction "1_1") (pintype "passive"))
      (node (ref "U1") (pin "47") (pinfunction "VCAP_2_47") (pintype "power_in"))
    )
    (net (code "46") (name "Net-(U2-BST)") (class "Default")
      (node (ref "C15") (pin "1") (pinfunction "1_1") (pintype "passive"))
      (node (ref "U2") (pin "1") (pinfunction "BST_1") (pintype "passive"))
    )
    (net (code "47") (name "Net-(U2-EN)") (class "Default")
      (node (ref "R2") (pin "1") (pinfunction "1_1") (pintype "passive"))
      (node (ref "U2") (pin "4") (pinfunction "EN_4") (pintype "passive"))
    )
    (net (code "48") (name "Net-(U2-FB)") (class "Default")
      (node (ref "R4") (pin "2") (pinfunction "2_2") (pintype "passive"))
      (node (ref "R5") (pin "2") (pinfunction "2_2") (pintype "passive"))
      (node (ref "U2") (pin "3") (pinfunction "FB_3") (pintype "passive"))
    )
    (net (code "49") (name "Net-(U3-BST)") (class "Default")
      (node (ref "C17") (pin "1") (pinfunction "1_1") (pintype "passive"))
      (node (ref "U3") (pin "1") (pinfunction "BST_1") (pintype "passive"))
    )
    (net (code "50") (name "Net-(U3-EN)") (class "Default")
      (node (ref "R3") (pin "2") (pinfunction "2_2") (pintype "passive"))
      (node (ref "U3") (pin "4") (pinfunction "EN_4") (pintype "passive"))
    )
    (net (code "51") (name "Net-(U3-FB)") (class "Default")
      (node (ref "C19") (pin "1") (pinfunction "1_1") (pintype "passive"))
      (node (ref "R6") (pin "1") (pinfunction "1_1") (pintype "passive"))
      (node (ref "R7") (pin "2") (pinfunction "2_2") (pintype "passive"))
      (node (ref "U3") (pin "3") (pinfunction "FB_3") (pintype "passive"))
    )
    (net (code "52") (name "Net-(U7-IN+)") (class "Default")
      (node (ref "C36") (pin "1") (pinfunction "1_1") (pintype "passive"))
      (node (ref "R19") (pin "1") (pinfunction "1_1") (pintype "passive"))
      (node (ref "U7") (pin "10") (pinfunction "IN+_10") (pintype "passive"))
    )
    (net (code "53") (name "Net-(U7-IN-)") (class "Default")
      (node (ref "C36") (pin "2") (pinfunction "2_2") (pintype "passive"))
      (node (ref "R18") (pin "1") (pinfunction "1_1") (pintype "passive"))
      (node (ref "U7") (pin "9") (pinfunction "IN-_9") (pintype "passive"))
    )
    (net (code "54") (name "Power_Cap") (class "Default")
      (node (ref "P2") (pin "1") (pinfunction "1_1") (pintype "passive"))
      (node (ref "Q5") (pin "3") (pinfunction "S_3") (pintype "passive"))
      (node (ref "R16") (pin "1") (pinfunction "1_1") (pintype "passive"))
      (node (ref "R17") (pin "1") (pinfunction "1_1") (pintype "passive"))
      (node (ref "R18") (pin "2") (pinfunction "2_2") (pintype "passive"))
      (node (ref "U7") (pin "8") (pinfunction "VBUS_8") (pintype "passive"))
    )
    (net (code "55") (name "Power_Charge") (class "Default")
      (node (ref "C34") (pin "1") (pinfunction "1_1") (pintype "passive"))
      (node (ref "C37") (pin "1") (pinfunction "1_1") (pintype "passive"))
      (node (ref "C38") (pin "1") (pinfunction "A_1") (pintype "passive"))
      (node (ref "D10") (pin "1") (pinfunction "A_1") (pintype "passive"))
      (node (ref "D9") (pin "1") (pinfunction "A_1") (pintype "passive"))
      (node (ref "L3") (pin "2") (pinfunction "2_2") (pintype "passive"))
      (node (ref "R22") (pin "2") (pinfunction "2_2") (pintype "passive"))
    )
    (net (code "56") (name "Power_Charge_out") (class "Default")
      (node (ref "D10") (pin "2") (pinfunction "K_2") (pintype "passive"))
      (node (ref "D9") (pin "2") (pinfunction "K_2") (pintype "passive"))
      (node (ref "R17") (pin "2") (pinfunction "2_2") (pintype "passive"))
      (node (ref "R19") (pin "2") (pinfunction "2_2") (pintype "passive"))
    )
    (net (code "57") (name "VCC_3.3V") (class "Default")
      (node (ref "C1") (pin "1") (pinfunction "1_1") (pintype "passive"))
      (node (ref "C2") (pin "1") (pinfunction "1_1") (pintype "passive"))
      (node (ref "C3") (pin "1") (pinfunction "1_1") (pintype "passive"))
      (node (ref "C30") (pin "1") (pinfunction "1_1") (pintype "passive"))
      (node (ref "C31") (pin "1") (pinfunction "1_1") (pintype "passive"))
      (node (ref "C35") (pin "1") (pinfunction "1_1") (pintype "passive"))
      (node (ref "C39") (pin "1") (pinfunction "1_1") (pintype "passive"))
      (node (ref "C4") (pin "1") (pinfunction "1_1") (pintype "passive"))
      (node (ref "C5") (pin "1") (pinfunction "1_1") (pintype "passive"))
      (node (ref "C6") (pin "1") (pinfunction "1_1") (pintype "passive"))
      (node (ref "C7") (pin "1") (pinfunction "1_1") (pintype "passive"))
      (node (ref "P7") (pin "4") (pinfunction "4_4") (pintype "passive"))
      (node (ref "R1") (pin "2") (pinfunction "2_2") (pintype "passive"))
      (node (ref "R20") (pin "2") (pinfunction "2_2") (pintype "passive"))
      (node (ref "R24") (pin "1") (pinfunction "1_1") (pintype "passive"))
      (node (ref "R25") (pin "2") (pinfunction "2_2") (pintype "passive"))
      (node (ref "R26") (pin "1") (pinfunction "1_1") (pintype "passive"))
      (node (ref "R27") (pin "1") (pinfunction "1_1") (pintype "passive"))
      (node (ref "U1") (pin "13") (pinfunction "VDDA_13") (pintype "power_in"))
      (node (ref "U1") (pin "19") (pinfunction "VDD_19") (pintype "power_in"))
      (node (ref "U1") (pin "32") (pinfunction "VDD_32") (pintype "power_in"))
      (node (ref "U1") (pin "48") (pinfunction "VDD_48") (pintype "power_in"))
      (node (ref "U1") (pin "64") (pinfunction "VDD_64") (pintype "power_in"))
      (node (ref "U4") (pin "5") (pinfunction "OUT_5") (pintype "passive"))
      (node (ref "U5") (pin "5") (pinfunction "VCC_5") (pintype "passive"))
      (node (ref "U6") (pin "3") (pinfunction "VCC_3") (pintype "passive"))
      (node (ref "U7") (pin "6") (pinfunction "VS_6") (pintype "passive"))
    )
    (net (code "58") (name "VCC_5V") (class "Default")
      (node (ref "C24") (pin "1") (pinfunction "1_1") (pintype "passive"))
      (node (ref "C25") (pin "1") (pinfunction "1_1") (pintype "passive"))
      (node (ref "C27") (pin "1") (pinfunction "1_1") (pintype "passive"))
      (node (ref "C28") (pin "1") (pinfunction "1_1") (pintype "passive"))
      (node (ref "L2") (pin "2") (pinfunction "2_2") (pintype "passive"))
      (node (ref "P6") (pin "4") (pinfunction "4_4") (pintype "passive"))
      (node (ref "R7") (pin "1") (pinfunction "1_1") (pintype "passive"))
      (node (ref "R8") (pin "1") (pinfunction "1_1") (pintype "passive"))
      (node (ref "U4") (pin "1") (pinfunction "IN_1") (pintype "passive"))
      (node (ref "U4") (pin "3") (pinfunction "EN_3") (pintype "passive"))
    )
    (net (code "59") (name "VCC_12V") (class "Default")
      (node (ref "C20") (pin "1") (pinfunction "1_1") (pintype "passive"))
      (node (ref "C21") (pin "1") (pinfunction "1_1") (pintype "passive"))
      (node (ref "C22") (pin "1") (pinfunction "1_1") (pintype "passive"))
      (node (ref "C23") (pin "1") (pinfunction "1_1") (pintype "passive"))
      (node (ref "C26") (pin "1") (pinfunction "1_1") (pintype "passive"))
      (node (ref "D3") (pin "1") (pinfunction "A_1") (pintype "passive"))
      (node (ref "L1") (pin "2") (pinfunction "2_2") (pintype "passive"))
      (node (ref "Q1") (pin "1") (pinfunction "VDD_1") (pintype "passive"))
      (node (ref "R5") (pin "1") (pinfunction "1_1") (pintype "passive"))
    )
    (net (code "60") (name "unconnected-(Q1-NC-Pad5)") (class "Default")
      (node (ref "Q1") (pin "5") (pinfunction "NC_5") (pintype "passive"))
    )
    (net (code "61") (name "unconnected-(U1A-PA0-WKUP(PA0){slash}USART2_CTS{slash}UART4_TX{slash}ETH_MII_CRS{slash}TIM2_CH1_ETR{slash}TIM5_CH1{slash}TIM8_ETR{slash}EVENTOUT{slash}ADC123_IN0{slash}WKUP-Pad14)") (class "Default")
      (node (ref "U1") (pin "14") (pinfunction "PA0-WKUP(PA0)/USART2_CTS/UART4_TX/ETH_MII_CRS/TIM2_CH1_ETR/TIM5_CH1/TIM8_ETR/EVENTOUT/ADC123_IN0/WKUP_14") (pintype "bidirectional"))
    )
    (net (code "62") (name "unconnected-(U1A-PA2{slash}USART2_TX{slash}TIM5_CH3{slash}TIM9_CH1{slash}TIM2_CH3{slash}ETH_MDIO{slash}EVENTOUT{slash}ADC123_IN2-Pad16)") (class "Default")
      (node (ref "U1") (pin "16") (pinfunction "PA2/USART2_TX/TIM5_CH3/TIM9_CH1/TIM2_CH3/ETH_MDIO/EVENTOUT/ADC123_IN2_16") (pintype "bidirectional"))
    )
    (net (code "63") (name "unconnected-(U1A-PA3{slash}USART2_RX{slash}TIM5_CH4{slash}TIM9_CH2{slash}TIM2_CH4{slash}OTG_HS_ULPI_D0{slash}ETH_MII_COL{slash}EVENTOUT{slash}ADC123_IN3-Pad17)") (class "Default")
      (node (ref "U1") (pin "17") (pinfunction "PA3/USART2_RX/TIM5_CH4/TIM9_CH2/TIM2_CH4/OTG_HS_ULPI_D0/ETH_MII_COL/EVENTOUT/ADC123_IN3_17") (pintype "bidirectional"))
    )
    (net (code "64") (name "unconnected-(U1A-PA4{slash}SPI1_NSS{slash}SPI3_NSS{slash}USART2_CK{slash}DCMI_HSYNC{slash}OTG_HS_SOF{slash}I2S3_WS{slash}EVENTOUT{slash}ADC12_IN4{slash}DAC1_OUT-Pad20)") (class "Default")
      (node (ref "U1") (pin "20") (pinfunction "PA4/SPI1_NSS/SPI3_NSS/USART2_CK/DCMI_HSYNC/OTG_HS_SOF/I2S3_WS/EVENTOUT/ADC12_IN4/DAC1_OUT_20") (pintype "bidirectional"))
    )
    (net (code "65") (name "unconnected-(U1A-PA5{slash}SPI1_SCK{slash}OTG_HS_ULPI_CK{slash}TIM2_CH1_ETR{slash}TIM8_CHIN{slash}EVENTOUT{slash}ADC12_IN5{slash}DAC2_OUT-Pad21)") (class "Default")
      (node (ref "U1") (pin "21") (pinfunction "PA5/SPI1_SCK/OTG_HS_ULPI_CK/TIM2_CH1_ETR/TIM8_CHIN/EVENTOUT/ADC12_IN5/DAC2_OUT_21") (pintype "bidirectional"))
    )
    (net (code "66") (name "unconnected-(U1A-PA6{slash}SPI1_MISO{slash}TIM8_BKIN{slash}TIM13_CH1{slash}DCMI_PIXCLK{slash}TIM3_CH1{slash}TIM1_BKIN{slash}EVENTOUT{slash}ADC12_IN6-Pad22)") (class "Default")
      (node (ref "U1") (pin "22") (pinfunction "PA6/SPI1_MISO/TIM8_BKIN/TIM13_CH1/DCMI_PIXCLK/TIM3_CH1/TIM1_BKIN/EVENTOUT/ADC12_IN6_22") (pintype "bidirectional"))
    )
    (net (code "67") (name "unconnected-(U1A-PA7{slash}SPI1_MOSI{slash}TIM8_CH1N{slash}TIM14_CH1{slash}TIM3_CH2{slash}ETH_MII_RX_DV{slash}TIM1_CH1N{slash}RMII_CRS_DV{slash}EVENTOUT{slash}ADC12_IN7-Pad23)") (class "Default")
      (node (ref "U1") (pin "23") (pinfunction "PA7/SPI1_MOSI/TIM8_CH1N/TIM14_CH1/TIM3_CH2/ETH_MII_RX_DV/TIM1_CH1N/RMII_CRS_DV/EVENTOUT/ADC12_IN7_23") (pintype "bidirectional"))
    )
    (net (code "68") (name "unconnected-(U1A-PA8{slash}MCO1{slash}USART1_CK{slash}TIM1_CH1{slash}I2C3_SCL{slash}OTG_FS_SOF{slash}EVENTOUT-Pad41)") (class "Default")
      (node (ref "U1") (pin "41") (pinfunction "PA8/MCO1/USART1_CK/TIM1_CH1/I2C3_SCL/OTG_FS_SOF/EVENTOUT_41") (pintype "bidirectional"))
    )
    (net (code "69") (name "unconnected-(U1A-PA9{slash}USART1_TX{slash}TIM1_CH2{slash}I2C3_SMBA{slash}DCMI_D0{slash}EVENTOUT{slash}OTG_FS_VBUS-Pad42)") (class "Default")
      (node (ref "U1") (pin "42") (pinfunction "PA9/USART1_TX/TIM1_CH2/I2C3_SMBA/DCMI_D0/EVENTOUT/OTG_FS_VBUS_42") (pintype "bidirectional"))
    )
    (net (code "70") (name "unconnected-(U1A-PA10{slash}USART1_RX{slash}TIM1_CH3{slash}OTG_FS_ID{slash}DCMI_D1{slash}EVENTOUT-Pad43)") (class "Default")
      (node (ref "U1") (pin "43") (pinfunction "PA10/USART1_RX/TIM1_CH3/OTG_FS_ID/DCMI_D1/EVENTOUT_43") (pintype "bidirectional"))
    )
    (net (code "71") (name "unconnected-(U1A-PB0{slash}TIM3_CH3{slash}TIM8_CH2N{slash}OTG_HS_ULPI_D1{slash}ETH_MII_RXD2{slash}TIM1_CH2N{slash}EVENTOUT{slash}ADC12_IN8-Pad26)") (class "Default")
      (node (ref "U1") (pin "26") (pinfunction "PB0/TIM3_CH3/TIM8_CH2N/OTG_HS_ULPI_D1/ETH_MII_RXD2/TIM1_CH2N/EVENTOUT/ADC12_IN8_26") (pintype "bidirectional"))
    )
    (net (code "72") (name "unconnected-(U1A-PB1{slash}TIM3_CH4{slash}TIM8_CH3N{slash}OTG_HS_ULPI_D2{slash}ETH_MII_RXD3{slash}OTG_HS_INTN{slash}TIM1_CH3N{slash}EVENTOUT{slash}ADC12_IN9-Pad27)") (class "Default")
      (node (ref "U1") (pin "27") (pinfunction "PB1/TIM3_CH4/TIM8_CH3N/OTG_HS_ULPI_D2/ETH_MII_RXD3/OTG_HS_INTN/TIM1_CH3N/EVENTOUT/ADC12_IN9_27") (pintype "bidirectional"))
    )
    (net (code "73") (name "unconnected-(U1A-PB2-BOOT1(PB2){slash}EVENTOUT-Pad28)") (class "Default")
      (node (ref "U1") (pin "28") (pinfunction "PB2-BOOT1(PB2)/EVENTOUT_28") (pintype "bidirectional"))
    )
    (net (code "74") (name "unconnected-(U1A-PB3(JTDO{slash}TRACESWO){slash}JTDO{slash}TRACESWO{slash}SPI3_SCK{slash}I2S3_CK{slash}TIM2_CH2{slash}SPI1_SCK{slash}EVENTOUT-Pad55)") (class "Default")
      (node (ref "U1") (pin "55") (pinfunction "PB3(JTDO/TRACESWO)/JTDO/TRACESWO/SPI3_SCK/I2S3_CK/TIM2_CH2/SPI1_SCK/EVENTOUT_55") (pintype "bidirectional"))
    )
    (net (code "75") (name "unconnected-(U1A-PB4(NJTRST){slash}NJTRST{slash}SPI3_MISO{slash}TIM3_CH1{slash}SPI1_MISO{slash}I2S3ext_SD{slash}EVENTOUT-Pad56)") (class "Default")
      (node (ref "U1") (pin "56") (pinfunction "PB4(NJTRST)/NJTRST/SPI3_MISO/TIM3_CH1/SPI1_MISO/I2S3ext_SD/EVENTOUT_56") (pintype "bidirectional"))
    )
    (net (code "76") (name "unconnected-(U1A-PB10{slash}SPI2_SCK{slash}I2S2_CK{slash}I2C2_SCL{slash}USART3_TX{slash}OTG_HS_ULPI_D3{slash}ETH_MII_RX_ER{slash}TIM2_CH3{slash}EVENTOUT-Pad29)") (class "Default")
      (node (ref "U1") (pin "29") (pinfunction "PB10/SPI2_SCK/I2S2_CK/I2C2_SCL/USART3_TX/OTG_HS_ULPI_D3/ETH_MII_RX_ER/TIM2_CH3/EVENTOUT_29") (pintype "bidirectional"))
    )
    (net (code "77") (name "unconnected-(U1A-PB11{slash}I2C2_SDA{slash}USART3_RX{slash}OTG_HS_ULPI_D4{slash}ETH_RMII_TX_EN{slash}ETH_MII_TX_EN{slash}TIM2_CH4{slash}EVENTOUT-Pad30)") (class "Default")
      (node (ref "U1") (pin "30") (pinfunction "PB11/I2C2_SDA/USART3_RX/OTG_HS_ULPI_D4/ETH_RMII_TX_EN/ETH_MII_TX_EN/TIM2_CH4/EVENTOUT_30") (pintype "bidirectional"))
    )
    (net (code "78") (name "unconnected-(U1A-PB12{slash}SPI2_NSS{slash}I2S2_WS{slash}I2C2_SMBA{slash}USART3_CK{slash}TIM1_BKIN{slash}CAN2_RX{slash}OTG_HS_ULPI_D5{slash}ETH_RMII_TXD0{slash}ETH_MII_TXD0{slash}OTG_HS_ID{slash}EVENTOUT-Pad33)") (class "Default")
      (node (ref "U1") (pin "33") (pinfunction "PB12/SPI2_NSS/I2S2_WS/I2C2_SMBA/USART3_CK/TIM1_BKIN/CAN2_RX/OTG_HS_ULPI_D5/ETH_RMII_TXD0/ETH_MII_TXD0/OTG_HS_ID/EVENTOUT_33") (pintype "bidirectional"))
    )
    (net (code "79") (name "unconnected-(U1A-PB13{slash}SPI2_SCK{slash}I2S2_CK{slash}USART3_CTS{slash}TIM1_CH1N{slash}CAN2_TX{slash}OTG_HS_ULPI_D6{slash}ETH_RMII_TXD1{slash}ETH_MII_TXD1{slash}EVENTOUT{slash}OTG_HS_VBUS-Pad34)") (class "Default")
      (node (ref "U1") (pin "34") (pinfunction "PB13/SPI2_SCK/I2S2_CK/USART3_CTS/TIM1_CH1N/CAN2_TX/OTG_HS_ULPI_D6/ETH_RMII_TXD1/ETH_MII_TXD1/EVENTOUT/OTG_HS_VBUS_34") (pintype "bidirectional"))
    )
    (net (code "80") (name "unconnected-(U1A-PB14{slash}SPI2_MISO{slash}TIM1_CH2N{slash}TIM12_CH1{slash}OTG_HS_DM{slash}USART3_RTS{slash}TIM8_CH2N{slash}I2S2ext_SD{slash}EVENTOUT-Pad35)") (class "Default")
      (node (ref "U1") (pin "35") (pinfunction "PB14/SPI2_MISO/TIM1_CH2N/TIM12_CH1/OTG_HS_DM/USART3_RTS/TIM8_CH2N/I2S2ext_SD/EVENTOUT_35") (pintype "bidirectional"))
    )
    (net (code "81") (name "unconnected-(U1A-PB15{slash}SPI2_MOSI{slash}I2S2_SD{slash}TIM1_CH3N{slash}TIM8_CH3N{slash}TIM12_CH2{slash}OTG_HS_DP{slash}EVENTOUT-Pad36)") (class "Default")
      (node (ref "U1") (pin "36") (pinfunction "PB15/SPI2_MOSI/I2S2_SD/TIM1_CH3N/TIM8_CH3N/TIM12_CH2/OTG_HS_DP/EVENTOUT_36") (pintype "bidirectional"))
    )
    (net (code "82") (name "unconnected-(U1B-PC0{slash}OTG_HS_ULPI_STP{slash}EVENTOUT{slash}ADC123_IN10-Pad8)") (class "Default")
      (node (ref "U1") (pin "8") (pinfunction "PC0/OTG_HS_ULPI_STP/EVENTOUT/ADC123_IN10_8") (pintype "bidirectional"))
    )
    (net (code "83") (name "unconnected-(U1B-PC1{slash}ETH_MDC{slash}EVENTOUT{slash}ADC123_IN11-Pad9)") (class "Default")
      (node (ref "U1") (pin "9") (pinfunction "PC1/ETH_MDC/EVENTOUT/ADC123_IN11_9") (pintype "bidirectional"))
    )
    (net (code "84") (name "unconnected-(U1B-PC2{slash}SPI2_MISO{slash}OTG_HS_ULPI_DIR{slash}TH_MII_TXD2{slash}I2S2ext_SD{slash}EVENTOUT{slash}ADC123_IN12-Pad10)") (class "Default")
      (node (ref "U1") (pin "10") (pinfunction "PC2/SPI2_MISO/OTG_HS_ULPI_DIR/TH_MII_TXD2/I2S2ext_SD/EVENTOUT/ADC123_IN12_10") (pintype "bidirectional"))
    )
    (net (code "85") (name "unconnected-(U1B-PC4{slash}ETH_RMII_RX_D0{slash}ETH_MII_RX_D0{slash}EVENTOUT{slash}ADC12_IN14-Pad24)") (class "Default")
      (node (ref "U1") (pin "24") (pinfunction "PC4/ETH_RMII_RX_D0/ETH_MII_RX_D0/EVENTOUT/ADC12_IN14_24") (pintype "bidirectional"))
    )
    (net (code "86") (name "unconnected-(U1B-PC5{slash}ETH_RMII_RX_D1{slash}ETH_MII_RX_D1{slash}EVENTOUT{slash}ADC12_IN15-Pad25)") (class "Default")
      (node (ref "U1") (pin "25") (pinfunction "PC5/ETH_RMII_RX_D1/ETH_MII_RX_D1/EVENTOUT/ADC12_IN15_25") (pintype "bidirectional"))
    )
    (net (code "87") (name "unconnected-(U1B-PC6{slash}I2S2_MCK{slash}TIM8_CH1{slash}SDIO_D6{slash}USART6_TX{slash}DCMI_D0{slash}TIM3_CH1{slash}EVENTOUT-Pad37)") (class "Default")
      (node (ref "U1") (pin "37") (pinfunction "PC6/I2S2_MCK/TIM8_CH1/SDIO_D6/USART6_TX/DCMI_D0/TIM3_CH1/EVENTOUT_37") (pintype "bidirectional"))
    )
    (net (code "88") (name "unconnected-(U1B-PC7{slash}I2S3_MCK{slash}TIM8_CH2{slash}SDIO_D7{slash}USART6_RX{slash}DCMI_D1{slash}TIM3_CH2{slash}EVENTOUT-Pad38)") (class "Default")
      (node (ref "U1") (pin "38") (pinfunction "PC7/I2S3_MCK/TIM8_CH2/SDIO_D7/USART6_RX/DCMI_D1/TIM3_CH2/EVENTOUT_38") (pintype "bidirectional"))
    )
    (net (code "89") (name "unconnected-(U1B-PC8{slash}TIM8_CH3{slash}SDIO_D0{slash}TIM3_CH3{slash}USART6_CK{slash}DCMI_D2{slash}EVENTOUT-Pad39)") (class "Default")
      (node (ref "U1") (pin "39") (pinfunction "PC8/TIM8_CH3/SDIO_D0/TIM3_CH3/USART6_CK/DCMI_D2/EVENTOUT_39") (pintype "bidirectional"))
    )
    (net (code "90") (name "unconnected-(U1B-PC9{slash}I2S_CKIN{slash}MCO2{slash}TIM8_CH4{slash}SDIO_D1{slash}{slash}I2C3_SDA{slash}DCMI_D3{slash}TIM3_CH4{slash}EVENTOUT-Pad40)") (class "Default")
      (node (ref "U1") (pin "40") (pinfunction "PC9/I2S_CKIN/MCO2/TIM8_CH4/SDIO_D1//I2C3_SDA/DCMI_D3/TIM3_CH4/EVENTOUT_40") (pintype "bidirectional"))
    )
    (net (code "91") (name "unconnected-(U1B-PC10{slash}SPI3_SCK{slash}I2S3_CK{slash}UART4_TX{slash}SDIO_D2{slash}DCMI_D8{slash}USART3_TX{slash}EVENTOUT-Pad51)") (class "Default")
      (node (ref "U1") (pin "51") (pinfunction "PC10/SPI3_SCK/I2S3_CK/UART4_TX/SDIO_D2/DCMI_D8/USART3_TX/EVENTOUT_51") (pintype "bidirectional"))
    )
    (net (code "92") (name "unconnected-(U1B-PC11{slash}UART4_RX{slash}SPI3_MISO{slash}SDIO_D3{slash}DCMI_D4{slash}USART3_RX{slash}I2S3ext_SD{slash}EVENTOUT-Pad52)") (class "Default")
      (node (ref "U1") (pin "52") (pinfunction "PC11/UART4_RX/SPI3_MISO/SDIO_D3/DCMI_D4/USART3_RX/I2S3ext_SD/EVENTOUT_52") (pintype "bidirectional"))
    )
    (net (code "93") (name "unconnected-(U1B-PC13{slash}EVENTOUT{slash}RTC_AF1-Pad2)") (class "Default")
      (node (ref "U1") (pin "2") (pinfunction "PC13/EVENTOUT/RTC_AF1_2") (pintype "bidirectional"))
    )
    (net (code "94") (name "unconnected-(U1B-PC14-OSC32_IN(PC14){slash}EVENTOUT{slash}OSC32_IN-Pad3)") (class "Default")
      (node (ref "U1") (pin "3") (pinfunction "PC14-OSC32_IN(PC14)/EVENTOUT/OSC32_IN_3") (pintype "bidirectional"))
    )
    (net (code "95") (name "unconnected-(U1B-PC15-OSC32_OUT(PC15){slash}EVENTOUT{slash}OSC32_OUT-Pad4)") (class "Default")
      (node (ref "U1") (pin "4") (pinfunction "PC15-OSC32_OUT(PC15)/EVENTOUT/OSC32_OUT_4") (pintype "bidirectional"))
    )
    (net (code "96") (name "unconnected-(U1D-VBAT-Pad1)") (class "Default")
      (node (ref "U1") (pin "1") (pinfunction "VBAT_1") (pintype "power_in+no_connect"))
    )
    (net (code "97") (name "unconnected-(U4-NC-Pad4)") (class "Default")
      (node (ref "U4") (pin "4") (pinfunction "NC_4") (pintype "passive"))
    )
    (net (code "98") (name "unconnected-(U6-Vref-Pad5)") (class "Default")
      (node (ref "U6") (pin "5") (pinfunction "Vref_5") (pintype "passive"))
    )
    (net (code "99") (name "unconnected-(U7-Alert-Pad3)") (class "Default")
      (node (ref "U7") (pin "3") (pinfunction "Alert_3") (pintype "passive"))
    )
  )
)
